# Pi-Breakout.net
KiCad netlist of a schematic drawn in EAGLE
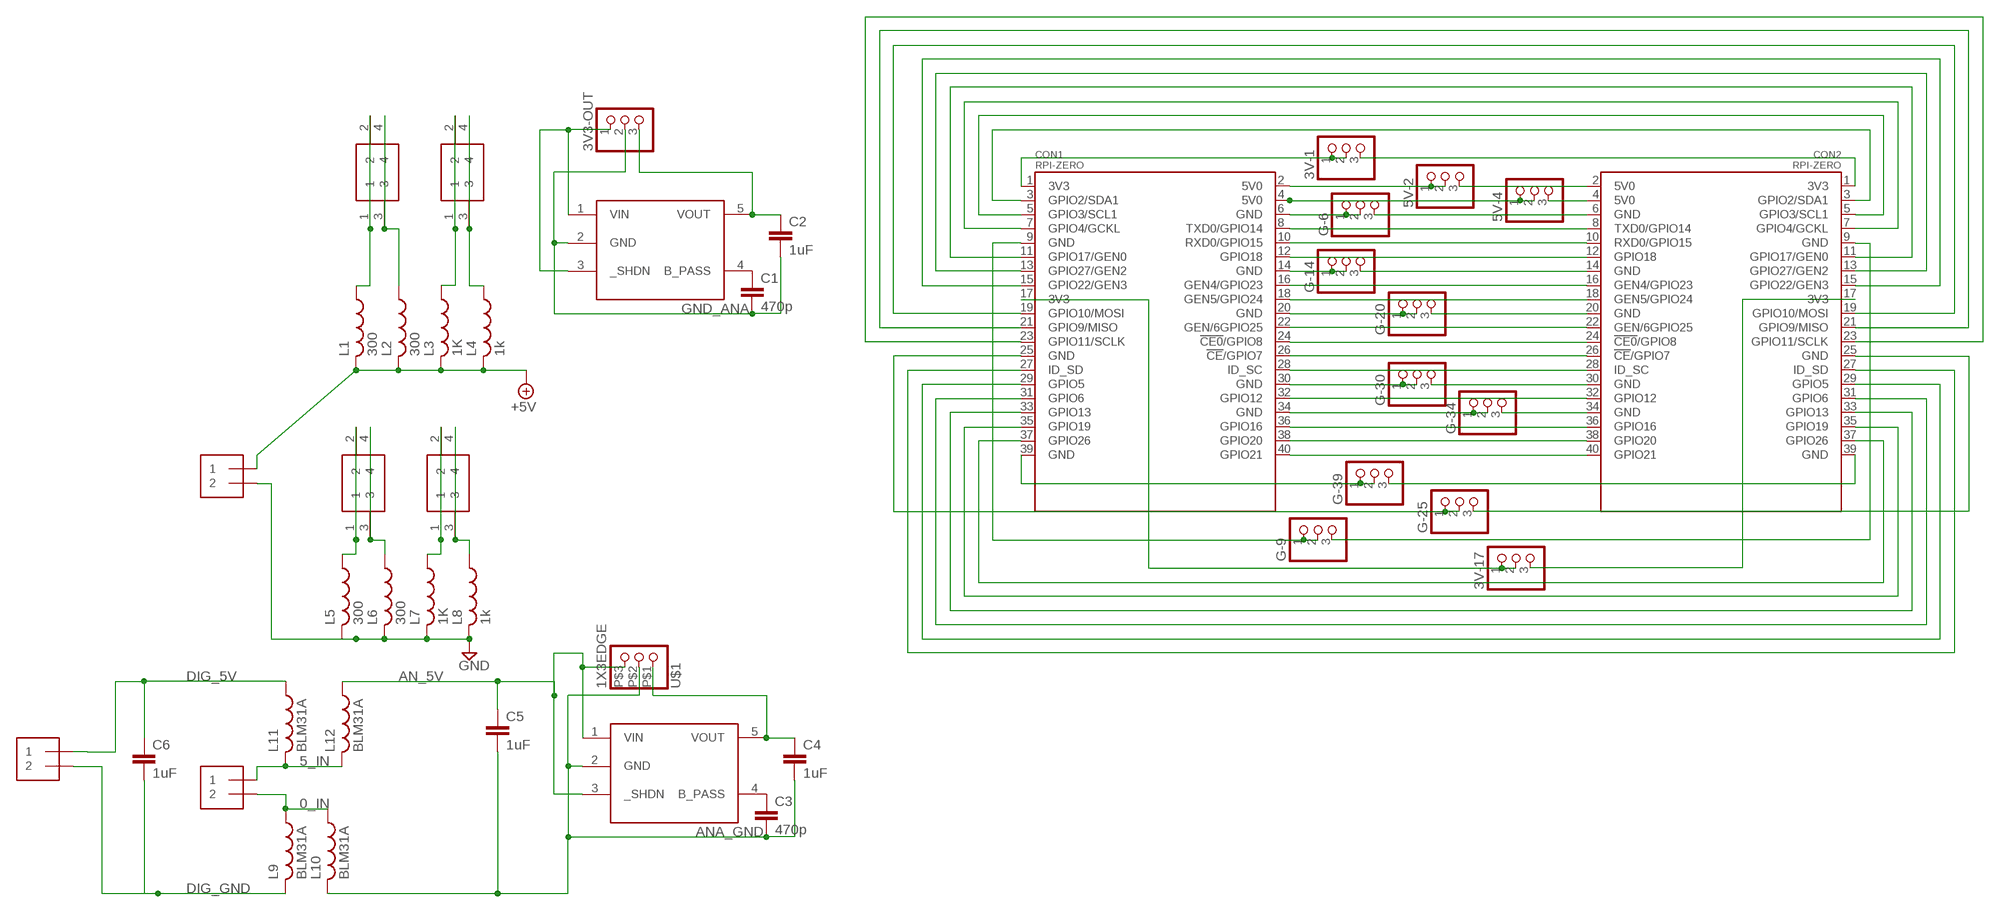
[diagram p0: schematic, sheet 1]

(export (version "E")
  (design (tool "Eeschema 10.0.6"))
  (components
    (comp (ref "3V-1")
      (value "PINHD-1X3")
      (footprint "eagle-import:1X03")
      (libsource (lib "eagle-import") (part "PINHD-1X3"))
    )
    (comp (ref "3V-17")
      (value "PINHD-1X3")
      (footprint "eagle-import:1X03")
      (libsource (lib "eagle-import") (part "PINHD-1X3"))
    )
    (comp (ref "3V3-OUT")
      (value "PINHD-1X3")
      (footprint "eagle-import:1X03")
      (libsource (lib "eagle-import") (part "PINHD-1X3"))
    )
    (comp (ref "5V-2")
      (value "PINHD-1X3")
      (footprint "eagle-import:1X03")
      (libsource (lib "eagle-import") (part "PINHD-1X3"))
    )
    (comp (ref "5V-4")
      (value "PINHD-1X3")
      (footprint "eagle-import:1X03")
      (libsource (lib "eagle-import") (part "PINHD-1X3"))
    )
    (comp (ref "5V1")
      (value "2X2HEADER")
      (footprint "eagle-import:2X2")
      (libsource (lib "eagle-import") (part "2X2HEADER"))
    )
    (comp (ref "5V2")
      (value "2X2HEADER")
      (footprint "eagle-import:2X2")
      (libsource (lib "eagle-import") (part "2X2HEADER"))
    )
    (comp (ref "C1")
      (value "470p")
      (footprint "eagle-import:C0603")
      (libsource (lib "eagle-import") (part "C-EUC0603"))
    )
    (comp (ref "C2")
      (value "1uF")
      (footprint "eagle-import:C0603")
      (libsource (lib "eagle-import") (part "C-EUC0603"))
    )
    (comp (ref "C3")
      (value "470p")
      (footprint "eagle-import:C0603")
      (libsource (lib "eagle-import") (part "C-EUC0603"))
    )
    (comp (ref "C4")
      (value "1uF")
      (footprint "eagle-import:C0603")
      (libsource (lib "eagle-import") (part "C-EUC0603"))
    )
    (comp (ref "C5")
      (value "1uF")
      (footprint "eagle-import:C0603")
      (libsource (lib "eagle-import") (part "C-EUC0603"))
    )
    (comp (ref "C6")
      (value "1uF")
      (footprint "eagle-import:C0603")
      (libsource (lib "eagle-import") (part "C-EUC0603"))
    )
    (comp (ref "CON1")
      (value "RPI-ZERO")
      (footprint "eagle-import:RASPBERRYPI_BASTELSTUBE_V13_RASPI_BOARD_B+_FULL")
      (fields (field (name "MPN") "ADA2243"))
      (libsource (lib "eagle-import") (part "RPI-ZERO"))
    )
    (comp (ref "CON2")
      (value "RPI-ZERO")
      (footprint "eagle-import:RASPBERRYPI_BASTELSTUBE_V13_RASPI_BOARD_B+_FULL")
      (fields (field (name "MPN") "ADA2243"))
      (libsource (lib "eagle-import") (part "RPI-ZERO"))
    )
    (comp (ref "G-6")
      (value "PINHD-1X3")
      (footprint "eagle-import:1X03")
      (libsource (lib "eagle-import") (part "PINHD-1X3"))
    )
    (comp (ref "G-9")
      (value "PINHD-1X3")
      (footprint "eagle-import:1X03")
      (libsource (lib "eagle-import") (part "PINHD-1X3"))
    )
    (comp (ref "G-14")
      (value "PINHD-1X3")
      (footprint "eagle-import:1X03")
      (libsource (lib "eagle-import") (part "PINHD-1X3"))
    )
    (comp (ref "G-20")
      (value "PINHD-1X3")
      (footprint "eagle-import:1X03")
      (libsource (lib "eagle-import") (part "PINHD-1X3"))
    )
    (comp (ref "G-25")
      (value "PINHD-1X3")
      (footprint "eagle-import:1X03")
      (libsource (lib "eagle-import") (part "PINHD-1X3"))
    )
    (comp (ref "G-30")
      (value "PINHD-1X3")
      (footprint "eagle-import:1X03")
      (libsource (lib "eagle-import") (part "PINHD-1X3"))
    )
    (comp (ref "G-34")
      (value "PINHD-1X3")
      (footprint "eagle-import:1X03")
      (libsource (lib "eagle-import") (part "PINHD-1X3"))
    )
    (comp (ref "G-39")
      (value "PINHD-1X3")
      (footprint "eagle-import:1X03")
      (libsource (lib "eagle-import") (part "PINHD-1X3"))
    )
    (comp (ref "GND1")
      (value "2X2HEADER")
      (footprint "eagle-import:2X2")
      (libsource (lib "eagle-import") (part "2X2HEADER"))
    )
    (comp (ref "GND2")
      (value "2X2HEADER")
      (footprint "eagle-import:2X2")
      (libsource (lib "eagle-import") (part "2X2HEADER"))
    )
    (comp (ref "J1")
      (value "2X1-LOCKING")
      (footprint "eagle-import:22-23-2021")
      (fields (field (name "MPN") "22-23-2021"))
      (libsource (lib "eagle-import") (part "2X1-LOCKING"))
    )
    (comp (ref "J2")
      (value "1X2EDGE")
      (footprint "eagle-import:1X2_EDGE")
      (libsource (lib "eagle-import") (part "1X2EDGE"))
    )
    (comp (ref "J3")
      (value "1X2EDGE")
      (footprint "eagle-import:1X2_EDGE")
      (libsource (lib "eagle-import") (part "1X2EDGE"))
    )
    (comp (ref "L1")
      (value "300")
      (footprint "eagle-import:SML1206")
      (libsource (lib "eagle-import") (part "BLM31A"))
    )
    (comp (ref "L2")
      (value "300")
      (footprint "eagle-import:SML1206")
      (libsource (lib "eagle-import") (part "BLM31A"))
    )
    (comp (ref "L3")
      (value "1K")
      (footprint "eagle-import:SML1206")
      (libsource (lib "eagle-import") (part "BLM31A"))
    )
    (comp (ref "L4")
      (value "1k")
      (footprint "eagle-import:SML1206")
      (libsource (lib "eagle-import") (part "BLM31A"))
    )
    (comp (ref "L5")
      (value "300")
      (footprint "eagle-import:SML1206")
      (libsource (lib "eagle-import") (part "BLM31A"))
    )
    (comp (ref "L6")
      (value "300")
      (footprint "eagle-import:SML1206")
      (libsource (lib "eagle-import") (part "BLM31A"))
    )
    (comp (ref "L7")
      (value "1K")
      (footprint "eagle-import:SML1206")
      (libsource (lib "eagle-import") (part "BLM31A"))
    )
    (comp (ref "L8")
      (value "1k")
      (footprint "eagle-import:SML1206")
      (libsource (lib "eagle-import") (part "BLM31A"))
    )
    (comp (ref "L9")
      (value "BLM31A")
      (footprint "eagle-import:SML1206")
      (libsource (lib "eagle-import") (part "BLM31A"))
    )
    (comp (ref "L10")
      (value "BLM31A")
      (footprint "eagle-import:SML1206")
      (libsource (lib "eagle-import") (part "BLM31A"))
    )
    (comp (ref "L11")
      (value "BLM31A")
      (footprint "eagle-import:SML1206")
      (libsource (lib "eagle-import") (part "BLM31A"))
    )
    (comp (ref "L12")
      (value "BLM31A")
      (footprint "eagle-import:SML1206")
      (libsource (lib "eagle-import") (part "BLM31A"))
    )
    (comp (ref "U$1")
      (value "1X3EDGE")
      (footprint "eagle-import:1X3_EDGE")
      (libsource (lib "eagle-import") (part "1X3EDGE"))
    )
    (comp (ref "U1")
      (value "TC1014-3.3V")
      (footprint "eagle-import:GHI-IC_SOT23-5(MICROCHIP)")
      (libsource (lib "eagle-import") (part "TC1014-3.3V"))
    )
    (comp (ref "U2")
      (value "TC1014-3.3V")
      (footprint "eagle-import:GHI-IC_SOT23-5(MICROCHIP)")
      (libsource (lib "eagle-import") (part "TC1014-3.3V"))
    )
  )
  (nets
    (net (code "1") (name "+5V") (class "Default")
      (node (ref "J1") (pin "1") (pinfunction "1_1") (pintype "passive"))
      (node (ref "L1") (pin "C") (pinfunction "2_C") (pintype "passive"))
      (node (ref "L2") (pin "C") (pinfunction "2_C") (pintype "passive"))
      (node (ref "L3") (pin "C") (pinfunction "2_C") (pintype "passive"))
      (node (ref "L4") (pin "C") (pinfunction "2_C") (pintype "passive"))
    )
    (net (code "2") (name "/0_IN") (class "Default")
      (node (ref "J2") (pin "P$2") (pinfunction "2_P$2") (pintype "passive"))
      (node (ref "L10") (pin "A") (pinfunction "1_A") (pintype "passive"))
      (node (ref "L9") (pin "A") (pinfunction "1_A") (pintype "passive"))
    )
    (net (code "3") (name "/5_IN") (class "Default")
      (node (ref "J2") (pin "P$1") (pinfunction "1_P$1") (pintype "passive"))
      (node (ref "L11") (pin "C") (pinfunction "2_C") (pintype "passive"))
      (node (ref "L12") (pin "C") (pinfunction "2_C") (pintype "passive"))
    )
    (net (code "4") (name "/ANA_GND") (class "Default")
      (node (ref "C3") (pin "2") (pinfunction "2_2") (pintype "passive"))
      (node (ref "C4") (pin "2") (pinfunction "2_2") (pintype "passive"))
      (node (ref "C5") (pin "2") (pinfunction "2_2") (pintype "passive"))
      (node (ref "L10") (pin "C") (pinfunction "2_C") (pintype "passive"))
      (node (ref "U$1") (pin "P$2") (pinfunction "2_P$2") (pintype "passive"))
      (node (ref "U2") (pin "2") (pinfunction "GND_2") (pintype "bidirectional"))
    )
    (net (code "5") (name "/AN_5V") (class "Default")
      (node (ref "C5") (pin "1") (pinfunction "1_1") (pintype "passive"))
      (node (ref "L12") (pin "A") (pinfunction "1_A") (pintype "passive"))
      (node (ref "U$1") (pin "P$3") (pinfunction "3_P$3") (pintype "passive"))
      (node (ref "U2") (pin "1") (pinfunction "VIN_1") (pintype "bidirectional"))
      (node (ref "U2") (pin "3") (pinfunction "_SHDN_3") (pintype "bidirectional"))
    )
    (net (code "6") (name "/DIG_5V") (class "Default")
      (node (ref "C6") (pin "1") (pinfunction "1_1") (pintype "passive"))
      (node (ref "J3") (pin "P$1") (pinfunction "1_P$1") (pintype "passive"))
      (node (ref "L11") (pin "A") (pinfunction "1_A") (pintype "passive"))
    )
    (net (code "7") (name "/DIG_GND") (class "Default")
      (node (ref "C6") (pin "2") (pinfunction "2_2") (pintype "passive"))
      (node (ref "J3") (pin "P$2") (pinfunction "2_P$2") (pintype "passive"))
      (node (ref "L9") (pin "C") (pinfunction "2_C") (pintype "passive"))
    )
    (net (code "8") (name "/GND_ANA") (class "Default")
      (node (ref "3V3-OUT") (pin "2") (pinfunction "2_2") (pintype "passive"))
      (node (ref "C1") (pin "2") (pinfunction "2_2") (pintype "passive"))
      (node (ref "C2") (pin "2") (pinfunction "2_2") (pintype "passive"))
      (node (ref "U1") (pin "2") (pinfunction "GND_2") (pintype "bidirectional"))
    )
    (net (code "9") (name "GND") (class "Default")
      (node (ref "J1") (pin "2") (pinfunction "2_2") (pintype "passive"))
      (node (ref "L5") (pin "C") (pinfunction "2_C") (pintype "passive"))
      (node (ref "L6") (pin "C") (pinfunction "2_C") (pintype "passive"))
      (node (ref "L7") (pin "C") (pinfunction "2_C") (pintype "passive"))
      (node (ref "L8") (pin "C") (pinfunction "2_C") (pintype "passive"))
    )
    (net (code "10") (name "Net-(3V-1-Pad1)") (class "Default")
      (node (ref "3V-1") (pin "1") (pinfunction "1_1") (pintype "passive"))
      (node (ref "3V-1") (pin "2") (pinfunction "2_2") (pintype "passive"))
      (node (ref "CON1") (pin "1") (pinfunction "3V3_1") (pintype "power_in"))
    )
    (net (code "11") (name "Net-(3V-1-Pad3)") (class "Default")
      (node (ref "3V-1") (pin "3") (pinfunction "3_3") (pintype "passive"))
      (node (ref "CON2") (pin "1") (pinfunction "3V3_1") (pintype "power_in"))
    )
    (net (code "12") (name "Net-(3V-17-Pad1)") (class "Default")
      (node (ref "3V-17") (pin "1") (pinfunction "1_1") (pintype "passive"))
      (node (ref "3V-17") (pin "2") (pinfunction "2_2") (pintype "passive"))
      (node (ref "CON1") (pin "17") (pinfunction "3V3_17") (pintype "power_in"))
    )
    (net (code "13") (name "Net-(3V-17-Pad3)") (class "Default")
      (node (ref "3V-17") (pin "3") (pinfunction "3_3") (pintype "passive"))
      (node (ref "CON2") (pin "17") (pinfunction "3V3_17") (pintype "power_in"))
    )
    (net (code "14") (name "Net-(5V-2-Pad1)") (class "Default")
      (node (ref "5V-2") (pin "1") (pinfunction "1_1") (pintype "passive"))
      (node (ref "5V-2") (pin "2") (pinfunction "2_2") (pintype "passive"))
      (node (ref "CON1") (pin "2") (pinfunction "5V0_2") (pintype "power_in"))
    )
    (net (code "15") (name "Net-(5V-2-Pad3)") (class "Default")
      (node (ref "5V-2") (pin "3") (pinfunction "3_3") (pintype "passive"))
      (node (ref "CON2") (pin "2") (pinfunction "5V0_2") (pintype "power_in"))
    )
    (net (code "16") (name "Net-(5V-4-Pad1)") (class "Default")
      (node (ref "5V-4") (pin "1") (pinfunction "1_1") (pintype "passive"))
      (node (ref "5V-4") (pin "2") (pinfunction "2_2") (pintype "passive"))
      (node (ref "CON1") (pin "4") (pinfunction "5V0_4") (pintype "power_in"))
    )
    (net (code "17") (name "Net-(5V-4-Pad3)") (class "Default")
      (node (ref "5V-4") (pin "3") (pinfunction "3_3") (pintype "passive"))
      (node (ref "CON2") (pin "4") (pinfunction "5V0_4") (pintype "power_in"))
    )
    (net (code "18") (name "Net-(CON1-GEN4{slash}GPIO23)") (class "Default")
      (node (ref "CON1") (pin "16") (pinfunction "GEN4/GPIO23_16") (pintype "bidirectional"))
      (node (ref "CON2") (pin "16") (pinfunction "GEN4/GPIO23_16") (pintype "bidirectional"))
    )
    (net (code "19") (name "Net-(CON1-GEN5{slash}GPIO24)") (class "Default")
      (node (ref "CON1") (pin "18") (pinfunction "GEN5/GPIO24_18") (pintype "bidirectional"))
      (node (ref "CON2") (pin "18") (pinfunction "GEN5/GPIO24_18") (pintype "bidirectional"))
    )
    (net (code "20") (name "Net-(CON1-GEN{slash}6GPIO25)") (class "Default")
      (node (ref "CON1") (pin "22") (pinfunction "GEN/6GPIO25_22") (pintype "bidirectional"))
      (node (ref "CON2") (pin "22") (pinfunction "GEN/6GPIO25_22") (pintype "bidirectional"))
    )
    (net (code "21") (name "Net-(CON1-GND-Pad6)") (class "Default")
      (node (ref "CON1") (pin "6") (pinfunction "GND_6") (pintype "power_in"))
      (node (ref "G-6") (pin "1") (pinfunction "1_1") (pintype "passive"))
      (node (ref "G-6") (pin "2") (pinfunction "2_2") (pintype "passive"))
    )
    (net (code "22") (name "Net-(CON1-GND-Pad9)") (class "Default")
      (node (ref "CON1") (pin "9") (pinfunction "GND_9") (pintype "power_in"))
      (node (ref "G-9") (pin "1") (pinfunction "1_1") (pintype "passive"))
      (node (ref "G-9") (pin "2") (pinfunction "2_2") (pintype "passive"))
    )
    (net (code "23") (name "Net-(CON1-GND-Pad14)") (class "Default")
      (node (ref "CON1") (pin "14") (pinfunction "GND_14") (pintype "power_in"))
      (node (ref "G-14") (pin "1") (pinfunction "1_1") (pintype "passive"))
      (node (ref "G-14") (pin "2") (pinfunction "2_2") (pintype "passive"))
    )
    (net (code "24") (name "Net-(CON1-GND-Pad20)") (class "Default")
      (node (ref "CON1") (pin "20") (pinfunction "GND_20") (pintype "power_in"))
      (node (ref "G-20") (pin "1") (pinfunction "1_1") (pintype "passive"))
      (node (ref "G-20") (pin "2") (pinfunction "2_2") (pintype "passive"))
    )
    (net (code "25") (name "Net-(CON1-GND-Pad25)") (class "Default")
      (node (ref "CON1") (pin "25") (pinfunction "GND_25") (pintype "power_in"))
      (node (ref "G-25") (pin "1") (pinfunction "1_1") (pintype "passive"))
      (node (ref "G-25") (pin "2") (pinfunction "2_2") (pintype "passive"))
    )
    (net (code "26") (name "Net-(CON1-GND-Pad30)") (class "Default")
      (node (ref "CON1") (pin "30") (pinfunction "GND_30") (pintype "power_in"))
      (node (ref "G-30") (pin "1") (pinfunction "1_1") (pintype "passive"))
      (node (ref "G-30") (pin "2") (pinfunction "2_2") (pintype "passive"))
    )
    (net (code "27") (name "Net-(CON1-GND-Pad34)") (class "Default")
      (node (ref "CON1") (pin "34") (pinfunction "GND_34") (pintype "power_in"))
      (node (ref "G-34") (pin "1") (pinfunction "1_1") (pintype "passive"))
      (node (ref "G-34") (pin "2") (pinfunction "2_2") (pintype "passive"))
    )
    (net (code "28") (name "Net-(CON1-GND-Pad39)") (class "Default")
      (node (ref "CON1") (pin "39") (pinfunction "GND_39") (pintype "power_in"))
      (node (ref "G-39") (pin "1") (pinfunction "1_1") (pintype "passive"))
      (node (ref "G-39") (pin "2") (pinfunction "2_2") (pintype "passive"))
    )
    (net (code "29") (name "Net-(CON1-GPIO2{slash}SDA1)") (class "Default")
      (node (ref "CON1") (pin "3") (pinfunction "GPIO2/SDA1_3") (pintype "bidirectional"))
      (node (ref "CON2") (pin "3") (pinfunction "GPIO2/SDA1_3") (pintype "bidirectional"))
    )
    (net (code "30") (name "Net-(CON1-GPIO3{slash}SCL1)") (class "Default")
      (node (ref "CON1") (pin "5") (pinfunction "GPIO3/SCL1_5") (pintype "bidirectional"))
      (node (ref "CON2") (pin "5") (pinfunction "GPIO3/SCL1_5") (pintype "bidirectional"))
    )
    (net (code "31") (name "Net-(CON1-GPIO4{slash}GCKL)") (class "Default")
      (node (ref "CON1") (pin "7") (pinfunction "GPIO4/GCKL_7") (pintype "bidirectional"))
      (node (ref "CON2") (pin "7") (pinfunction "GPIO4/GCKL_7") (pintype "bidirectional"))
    )
    (net (code "32") (name "Net-(CON1-GPIO5)") (class "Default")
      (node (ref "CON1") (pin "29") (pinfunction "GPIO5_29") (pintype "bidirectional"))
      (node (ref "CON2") (pin "29") (pinfunction "GPIO5_29") (pintype "bidirectional"))
    )
    (net (code "33") (name "Net-(CON1-GPIO6)") (class "Default")
      (node (ref "CON1") (pin "31") (pinfunction "GPIO6_31") (pintype "bidirectional"))
      (node (ref "CON2") (pin "31") (pinfunction "GPIO6_31") (pintype "bidirectional"))
    )
    (net (code "34") (name "Net-(CON1-GPIO9{slash}MISO)") (class "Default")
      (node (ref "CON1") (pin "21") (pinfunction "GPIO9/MISO_21") (pintype "bidirectional"))
      (node (ref "CON2") (pin "21") (pinfunction "GPIO9/MISO_21") (pintype "bidirectional"))
    )
    (net (code "35") (name "Net-(CON1-GPIO10{slash}MOSI)") (class "Default")
      (node (ref "CON1") (pin "19") (pinfunction "GPIO10/MOSI_19") (pintype "bidirectional"))
      (node (ref "CON2") (pin "19") (pinfunction "GPIO10/MOSI_19") (pintype "bidirectional"))
    )
    (net (code "36") (name "Net-(CON1-GPIO11{slash}SCLK)") (class "Default")
      (node (ref "CON1") (pin "23") (pinfunction "GPIO11/SCLK_23") (pintype "bidirectional"))
      (node (ref "CON2") (pin "23") (pinfunction "GPIO11/SCLK_23") (pintype "bidirectional"))
    )
    (net (code "37") (name "Net-(CON1-GPIO12)") (class "Default")
      (node (ref "CON1") (pin "32") (pinfunction "GPIO12_32") (pintype "bidirectional"))
      (node (ref "CON2") (pin "32") (pinfunction "GPIO12_32") (pintype "bidirectional"))
    )
    (net (code "38") (name "Net-(CON1-GPIO13)") (class "Default")
      (node (ref "CON1") (pin "33") (pinfunction "GPIO13_33") (pintype "bidirectional"))
      (node (ref "CON2") (pin "33") (pinfunction "GPIO13_33") (pintype "bidirectional"))
    )
    (net (code "39") (name "Net-(CON1-GPIO16)") (class "Default")
      (node (ref "CON1") (pin "36") (pinfunction "GPIO16_36") (pintype "bidirectional"))
      (node (ref "CON2") (pin "36") (pinfunction "GPIO16_36") (pintype "bidirectional"))
    )
    (net (code "40") (name "Net-(CON1-GPIO17{slash}GEN0)") (class "Default")
      (node (ref "CON1") (pin "11") (pinfunction "GPIO17/GEN0_11") (pintype "bidirectional"))
      (node (ref "CON2") (pin "11") (pinfunction "GPIO17/GEN0_11") (pintype "bidirectional"))
    )
    (net (code "41") (name "Net-(CON1-GPIO18)") (class "Default")
      (node (ref "CON1") (pin "12") (pinfunction "GPIO18_12") (pintype "bidirectional"))
      (node (ref "CON2") (pin "12") (pinfunction "GPIO18_12") (pintype "bidirectional"))
    )
    (net (code "42") (name "Net-(CON1-GPIO19)") (class "Default")
      (node (ref "CON1") (pin "35") (pinfunction "GPIO19_35") (pintype "bidirectional"))
      (node (ref "CON2") (pin "35") (pinfunction "GPIO19_35") (pintype "bidirectional"))
    )
    (net (code "43") (name "Net-(CON1-GPIO20)") (class "Default")
      (node (ref "CON1") (pin "38") (pinfunction "GPIO20_38") (pintype "bidirectional"))
      (node (ref "CON2") (pin "38") (pinfunction "GPIO20_38") (pintype "bidirectional"))
    )
    (net (code "44") (name "Net-(CON1-GPIO21)") (class "Default")
      (node (ref "CON1") (pin "40") (pinfunction "GPIO21_40") (pintype "bidirectional"))
      (node (ref "CON2") (pin "40") (pinfunction "GPIO21_40") (pintype "bidirectional"))
    )
    (net (code "45") (name "Net-(CON1-GPIO22{slash}GEN3)") (class "Default")
      (node (ref "CON1") (pin "15") (pinfunction "GPIO22/GEN3_15") (pintype "bidirectional"))
      (node (ref "CON2") (pin "15") (pinfunction "GPIO22/GEN3_15") (pintype "bidirectional"))
    )
    (net (code "46") (name "Net-(CON1-GPIO26)") (class "Default")
      (node (ref "CON1") (pin "37") (pinfunction "GPIO26_37") (pintype "bidirectional"))
      (node (ref "CON2") (pin "37") (pinfunction "GPIO26_37") (pintype "bidirectional"))
    )
    (net (code "47") (name "Net-(CON1-GPIO27{slash}GEN2)") (class "Default")
      (node (ref "CON1") (pin "13") (pinfunction "GPIO27/GEN2_13") (pintype "bidirectional"))
      (node (ref "CON2") (pin "13") (pinfunction "GPIO27/GEN2_13") (pintype "bidirectional"))
    )
    (net (code "48") (name "Net-(CON1-ID_SC)") (class "Default")
      (node (ref "CON1") (pin "28") (pinfunction "ID_SC_28") (pintype "bidirectional"))
      (node (ref "CON2") (pin "28") (pinfunction "ID_SC_28") (pintype "bidirectional"))
    )
    (net (code "49") (name "Net-(CON1-ID_SD)") (class "Default")
      (node (ref "CON1") (pin "27") (pinfunction "ID_SD_27") (pintype "bidirectional"))
      (node (ref "CON2") (pin "27") (pinfunction "ID_SD_27") (pintype "bidirectional"))
    )
    (net (code "50") (name "Net-(CON1-RXD0{slash}GPIO15)") (class "Default")
      (node (ref "CON1") (pin "10") (pinfunction "RXD0/GPIO15_10") (pintype "bidirectional"))
      (node (ref "CON2") (pin "10") (pinfunction "RXD0/GPIO15_10") (pintype "bidirectional"))
    )
    (net (code "51") (name "Net-(CON1-TXD0{slash}GPIO14)") (class "Default")
      (node (ref "CON1") (pin "8") (pinfunction "TXD0/GPIO14_8") (pintype "bidirectional"))
      (node (ref "CON2") (pin "8") (pinfunction "TXD0/GPIO14_8") (pintype "bidirectional"))
    )
    (net (code "52") (name "Net-(CON1-~{CE0}{slash}GPIO8)") (class "Default")
      (node (ref "CON1") (pin "24") (pinfunction "~{CE0}/GPIO8_24") (pintype "bidirectional"))
      (node (ref "CON2") (pin "24") (pinfunction "~{CE0}/GPIO8_24") (pintype "bidirectional"))
    )
    (net (code "53") (name "Net-(CON1-~{CE}{slash}GPIO7)") (class "Default")
      (node (ref "CON1") (pin "26") (pinfunction "~{CE}/GPIO7_26") (pintype "bidirectional"))
      (node (ref "CON2") (pin "26") (pinfunction "~{CE}/GPIO7_26") (pintype "bidirectional"))
    )
    (net (code "54") (name "Net-(CON2-GND-Pad6)") (class "Default")
      (node (ref "CON2") (pin "6") (pinfunction "GND_6") (pintype "power_in"))
      (node (ref "G-6") (pin "3") (pinfunction "3_3") (pintype "passive"))
    )
    (net (code "55") (name "Net-(CON2-GND-Pad9)") (class "Default")
      (node (ref "CON2") (pin "9") (pinfunction "GND_9") (pintype "power_in"))
      (node (ref "G-9") (pin "3") (pinfunction "3_3") (pintype "passive"))
    )
    (net (code "56") (name "Net-(CON2-GND-Pad14)") (class "Default")
      (node (ref "CON2") (pin "14") (pinfunction "GND_14") (pintype "power_in"))
      (node (ref "G-14") (pin "3") (pinfunction "3_3") (pintype "passive"))
    )
    (net (code "57") (name "Net-(CON2-GND-Pad20)") (class "Default")
      (node (ref "CON2") (pin "20") (pinfunction "GND_20") (pintype "power_in"))
      (node (ref "G-20") (pin "3") (pinfunction "3_3") (pintype "passive"))
    )
    (net (code "58") (name "Net-(CON2-GND-Pad25)") (class "Default")
      (node (ref "CON2") (pin "25") (pinfunction "GND_25") (pintype "power_in"))
      (node (ref "G-25") (pin "3") (pinfunction "3_3") (pintype "passive"))
    )
    (net (code "59") (name "Net-(CON2-GND-Pad30)") (class "Default")
      (node (ref "CON2") (pin "30") (pinfunction "GND_30") (pintype "power_in"))
      (node (ref "G-30") (pin "3") (pinfunction "3_3") (pintype "passive"))
    )
    (net (code "60") (name "Net-(CON2-GND-Pad34)") (class "Default")
      (node (ref "CON2") (pin "34") (pinfunction "GND_34") (pintype "power_in"))
      (node (ref "G-34") (pin "3") (pinfunction "3_3") (pintype "passive"))
    )
    (net (code "61") (name "Net-(CON2-GND-Pad39)") (class "Default")
      (node (ref "CON2") (pin "39") (pinfunction "GND_39") (pintype "power_in"))
      (node (ref "G-39") (pin "3") (pinfunction "3_3") (pintype "passive"))
    )
    (net (code "62") (name "Net-(L1-1)") (class "Default")
      (node (ref "5V1") (pin "1") (pinfunction "1_1") (pintype "bidirectional"))
      (node (ref "5V1") (pin "2") (pinfunction "2_2") (pintype "bidirectional"))
      (node (ref "L1") (pin "A") (pinfunction "1_A") (pintype "passive"))
    )
    (net (code "63") (name "Net-(L2-1)") (class "Default")
      (node (ref "5V1") (pin "3") (pinfunction "3_3") (pintype "bidirectional"))
      (node (ref "5V1") (pin "4") (pinfunction "4_4") (pintype "bidirectional"))
      (node (ref "L2") (pin "A") (pinfunction "1_A") (pintype "passive"))
    )
    (net (code "64") (name "Net-(L3-1)") (class "Default")
      (node (ref "5V2") (pin "1") (pinfunction "1_1") (pintype "bidirectional"))
      (node (ref "5V2") (pin "2") (pinfunction "2_2") (pintype "bidirectional"))
      (node (ref "L3") (pin "A") (pinfunction "1_A") (pintype "passive"))
    )
    (net (code "65") (name "Net-(L4-1)") (class "Default")
      (node (ref "5V2") (pin "3") (pinfunction "3_3") (pintype "bidirectional"))
      (node (ref "5V2") (pin "4") (pinfunction "4_4") (pintype "bidirectional"))
      (node (ref "L4") (pin "A") (pinfunction "1_A") (pintype "passive"))
    )
    (net (code "66") (name "Net-(L5-1)") (class "Default")
      (node (ref "GND1") (pin "1") (pinfunction "1_1") (pintype "bidirectional"))
      (node (ref "GND1") (pin "2") (pinfunction "2_2") (pintype "bidirectional"))
      (node (ref "L5") (pin "A") (pinfunction "1_A") (pintype "passive"))
    )
    (net (code "67") (name "Net-(L6-1)") (class "Default")
      (node (ref "GND1") (pin "3") (pinfunction "3_3") (pintype "bidirectional"))
      (node (ref "GND1") (pin "4") (pinfunction "4_4") (pintype "bidirectional"))
      (node (ref "L6") (pin "A") (pinfunction "1_A") (pintype "passive"))
    )
    (net (code "68") (name "Net-(L7-1)") (class "Default")
      (node (ref "GND2") (pin "1") (pinfunction "1_1") (pintype "bidirectional"))
      (node (ref "GND2") (pin "2") (pinfunction "2_2") (pintype "bidirectional"))
      (node (ref "L7") (pin "A") (pinfunction "1_A") (pintype "passive"))
    )
    (net (code "69") (name "Net-(L8-1)") (class "Default")
      (node (ref "GND2") (pin "3") (pinfunction "3_3") (pintype "bidirectional"))
      (node (ref "GND2") (pin "4") (pinfunction "4_4") (pintype "bidirectional"))
      (node (ref "L8") (pin "A") (pinfunction "1_A") (pintype "passive"))
    )
    (net (code "70") (name "Net-(U$1-1)") (class "Default")
      (node (ref "C4") (pin "1") (pinfunction "1_1") (pintype "passive"))
      (node (ref "U$1") (pin "P$1") (pinfunction "1_P$1") (pintype "passive"))
      (node (ref "U2") (pin "5") (pinfunction "VOUT_5") (pintype "bidirectional"))
    )
    (net (code "71") (name "Net-(U1-B_PASS)") (class "Default")
      (node (ref "C1") (pin "1") (pinfunction "1_1") (pintype "passive"))
      (node (ref "U1") (pin "4") (pinfunction "B_PASS_4") (pintype "bidirectional"))
    )
    (net (code "72") (name "Net-(U1-VIN)") (class "Default")
      (node (ref "3V3-OUT") (pin "1") (pinfunction "1_1") (pintype "passive"))
      (node (ref "U1") (pin "1") (pinfunction "VIN_1") (pintype "bidirectional"))
      (node (ref "U1") (pin "3") (pinfunction "_SHDN_3") (pintype "bidirectional"))
    )
    (net (code "73") (name "Net-(U1-VOUT)") (class "Default")
      (node (ref "3V3-OUT") (pin "3") (pinfunction "3_3") (pintype "passive"))
      (node (ref "C2") (pin "1") (pinfunction "1_1") (pintype "passive"))
      (node (ref "U1") (pin "5") (pinfunction "VOUT_5") (pintype "bidirectional"))
    )
    (net (code "74") (name "Net-(U2-B_PASS)") (class "Default")
      (node (ref "C3") (pin "1") (pinfunction "1_1") (pintype "passive"))
      (node (ref "U2") (pin "4") (pinfunction "B_PASS_4") (pintype "bidirectional"))
    )
  )
)
